# max3107.net
KiCad netlist of a schematic drawn in Altium Designer
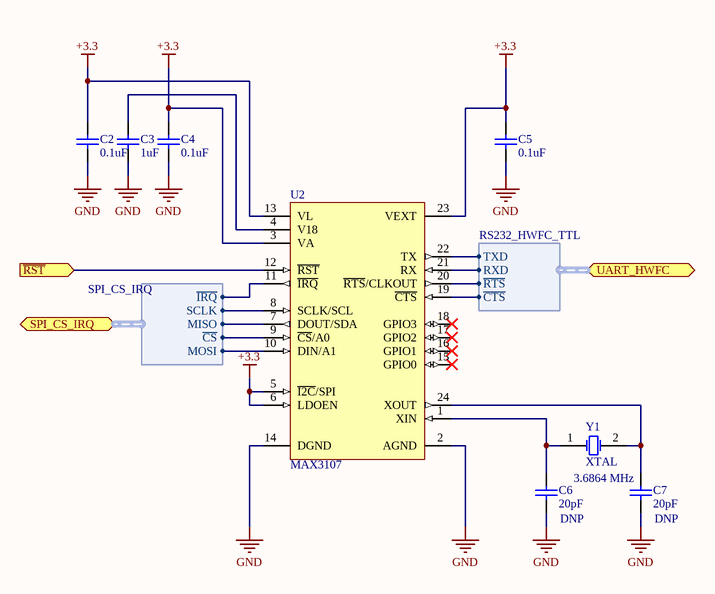
[diagram p0: max3107.SchDoc]

(export (version "E")
  (design (tool "Eeschema 10.0.6"))
  (components
    (comp (ref "C2")
      (value "0.1uF")
      (footprint "C0603")
      (description "Capacitor")
      (fields (field (name "Comment") "Cap"))
      (libsource (lib "Miscellaneous Devices") (part "Cap"))
    )
    (comp (ref "C3")
      (value "1uF")
      (footprint "C0603")
      (description "Capacitor")
      (fields (field (name "Comment") "Cap") (field (name "PUBLISHER") "Altium Limited"))
      (libsource (lib "Miscellaneous Devices") (part "Cap"))
    )
    (comp (ref "C4")
      (value "0.1uF")
      (footprint "C0603")
      (description "Capacitor")
      (fields (field (name "Comment") "Cap"))
      (libsource (lib "Miscellaneous Devices") (part "Cap"))
    )
    (comp (ref "C5")
      (value "0.1uF")
      (footprint "C0603")
      (description "Capacitor")
      (fields (field (name "Comment") "Cap"))
      (libsource (lib "Miscellaneous Devices") (part "Cap"))
    )
    (comp (ref "C6")
      (value "20pF")
      (footprint "C0603")
      (description "Capacitor")
      (fields (field (name "PLACE") "DNP") (field (name "Comment") "Cap"))
      (libsource (lib "Miscellaneous Devices") (part "Cap"))
    )
    (comp (ref "C7")
      (value "20pF")
      (footprint "C0603")
      (description "Capacitor")
      (fields (field (name "PLACE") "DNP") (field (name "Comment") "Cap"))
      (libsource (lib "Miscellaneous Devices") (part "Cap"))
    )
    (comp (ref "U2")
      (value "MAX3107")
      (footprint "MAX3107")
      (description "Maxim Integrated MAX3107EAG+")
      (libsource (lib "MAX3107") (part "MAX3107"))
    )
    (comp (ref "Y1")
      (value "XTAL")
      (footprint "FQ1045A-3.6864")
      (description "Crystal Oscillator")
      (fields (field (name "ALTIUM_VALUE") "3.6864 MHz") (field (name "PUBLISHER") "Altium Limited"))
      (libsource (lib "Miscellaneous Devices") (part "XTAL"))
    )
  )
  (nets
    (net (code "3") (name "+3.3") (class "Default")
      (node (ref "C2") (pin "1") (pinfunction "1_1") (pintype "passive"))
      (node (ref "C4") (pin "1") (pinfunction "1_1") (pintype "passive"))
      (node (ref "C5") (pin "1") (pinfunction "1_1") (pintype "passive"))
      (node (ref "U2") (pin "13") (pinfunction "VL_13") (pintype "power_in"))
      (node (ref "U2") (pin "23") (pinfunction "VEXT_23") (pintype "power_in"))
      (node (ref "U2") (pin "3") (pinfunction "VA_3") (pintype "power_in"))
      (node (ref "U2") (pin "5") (pinfunction "~{I2C}/SPI_5") (pintype "input"))
      (node (ref "U2") (pin "6") (pinfunction "LDOEN_6") (pintype "input"))
    )
    (net (code "4") (name "/MISO") (class "Default")
      (node (ref "U2") (pin "7") (pinfunction "DOUT/SDA_7") (pintype "output"))
    )
    (net (code "5") (name "/MOSI") (class "Default")
      (node (ref "U2") (pin "10") (pinfunction "DIN/A1_10") (pintype "input"))
    )
    (net (code "6") (name "/RXD") (class "Default")
      (node (ref "U2") (pin "21") (pinfunction "RX_21") (pintype "input"))
    )
    (net (code "7") (name "/SCLK") (class "Default")
      (node (ref "U2") (pin "8") (pinfunction "SCLK/SCL_8") (pintype "input"))
    )
    (net (code "8") (name "/TXD") (class "Default")
      (node (ref "U2") (pin "22") (pinfunction "TX_22") (pintype "output"))
    )
    (net (code "11") (name "/~{CS}") (class "Default")
      (node (ref "U2") (pin "9") (pinfunction "~{CS}/A0_9") (pintype "input"))
    )
    (net (code "12") (name "/~{CTS}") (class "Default")
      (node (ref "U2") (pin "19") (pinfunction "~{CTS}_19") (pintype "input"))
    )
    (net (code "13") (name "/~{IRQ}") (class "Default")
      (node (ref "U2") (pin "11") (pinfunction "~{IRQ}_11") (pintype "output"))
    )
    (net (code "14") (name "/~{RST}") (class "Default")
      (node (ref "U2") (pin "12") (pinfunction "~{RST}_12") (pintype "input"))
    )
    (net (code "15") (name "/~{RTS}") (class "Default")
      (node (ref "U2") (pin "20") (pinfunction "~{RTS}/CLKOUT_20") (pintype "output"))
    )
    (net (code "16") (name "GND") (class "Default")
      (node (ref "C2") (pin "2") (pinfunction "2_2") (pintype "passive"))
      (node (ref "C3") (pin "1") (pinfunction "1_1") (pintype "passive"))
      (node (ref "C4") (pin "2") (pinfunction "2_2") (pintype "passive"))
      (node (ref "C5") (pin "2") (pinfunction "2_2") (pintype "passive"))
      (node (ref "C6") (pin "2") (pinfunction "2_2") (pintype "passive"))
      (node (ref "C7") (pin "2") (pinfunction "2_2") (pintype "passive"))
      (node (ref "U2") (pin "14") (pinfunction "DGND_14") (pintype "power_in"))
      (node (ref "U2") (pin "2") (pinfunction "AGND_2") (pintype "power_in"))
    )
    (net (code "17") (name "Net-(U2-V18)") (class "Default")
      (node (ref "C3") (pin "2") (pinfunction "2_2") (pintype "passive"))
      (node (ref "U2") (pin "4") (pinfunction "V18_4") (pintype "power_in"))
    )
    (net (code "18") (name "Net-(U2-XIN)") (class "Default")
      (node (ref "C6") (pin "1") (pinfunction "1_1") (pintype "passive"))
      (node (ref "U2") (pin "1") (pinfunction "XIN_1") (pintype "input"))
      (node (ref "Y1") (pin "1") (pinfunction "OSC1_1") (pintype "passive"))
    )
    (net (code "19") (name "Net-(U2-XOUT)") (class "Default")
      (node (ref "C7") (pin "1") (pinfunction "1_1") (pintype "passive"))
      (node (ref "U2") (pin "24") (pinfunction "XOUT_24") (pintype "output"))
      (node (ref "Y1") (pin "2") (pinfunction "OSC2_2") (pintype "passive"))
    )
    (net (code "20") (name "unconnected-(U2-GPIO0-Pad15)") (class "Default")
      (node (ref "U2") (pin "15") (pinfunction "GPIO0_15") (pintype "bidirectional+no_connect"))
    )
    (net (code "21") (name "unconnected-(U2-GPIO1-Pad16)") (class "Default")
      (node (ref "U2") (pin "16") (pinfunction "GPIO1_16") (pintype "bidirectional+no_connect"))
    )
    (net (code "22") (name "unconnected-(U2-GPIO2-Pad17)") (class "Default")
      (node (ref "U2") (pin "17") (pinfunction "GPIO2_17") (pintype "bidirectional+no_connect"))
    )
    (net (code "23") (name "unconnected-(U2-GPIO3-Pad18)") (class "Default")
      (node (ref "U2") (pin "18") (pinfunction "GPIO3_18") (pintype "bidirectional+no_connect"))
    )
  )
)
